# 4809-dip-th.net
KiCad netlist of a schematic drawn in EAGLE
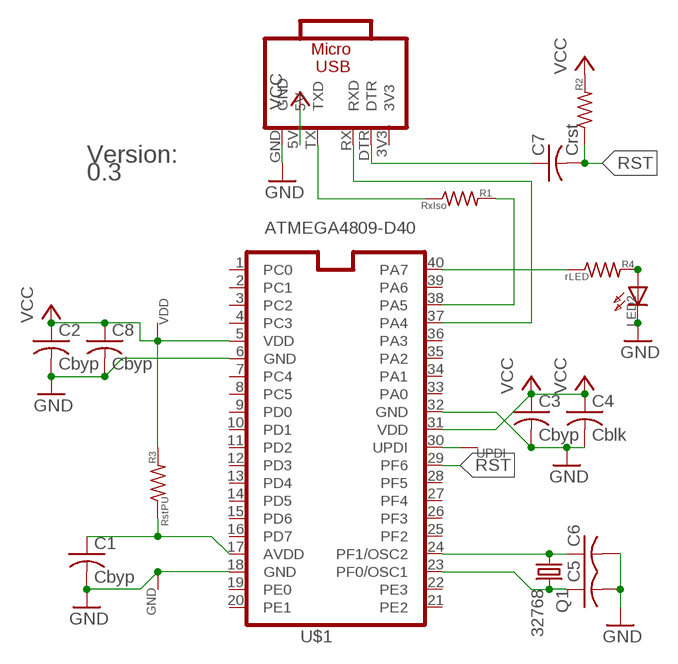
[diagram p0: schematic, sheet 1]

(export (version "E")
  (design (tool "Eeschema 10.0.6"))
  (components
    (comp (ref "C1")
      (value "Cbyp")
      (footprint "eagle-import:C025-025X050")
      (libsource (lib "eagle-import") (part "C-US-2.5MM"))
    )
    (comp (ref "C2")
      (value "Cbyp")
      (footprint "eagle-import:C025-025X050")
      (libsource (lib "eagle-import") (part "C-US-2.5MM"))
    )
    (comp (ref "C3")
      (value "Cbyp")
      (footprint "eagle-import:C025-025X050")
      (libsource (lib "eagle-import") (part "C-US-2.5MM"))
    )
    (comp (ref "C4")
      (value "Cblk")
      (footprint "eagle-import:C025-025X050")
      (libsource (lib "eagle-import") (part "C-US-2.5MM"))
    )
    (comp (ref "C5")
      (value "C-US-2.5MM")
      (footprint "eagle-import:C025-025X050")
      (libsource (lib "eagle-import") (part "C-US-2.5MM"))
    )
    (comp (ref "C6")
      (value "C-US-2.5MM")
      (footprint "eagle-import:C025-025X050")
      (libsource (lib "eagle-import") (part "C-US-2.5MM"))
    )
    (comp (ref "C7")
      (value "Crst")
      (footprint "eagle-import:C025-025X050")
      (libsource (lib "eagle-import") (part "C-US-2.5MM"))
    )
    (comp (ref "C8")
      (value "Cbyp")
      (footprint "eagle-import:C1206")
      (libsource (lib "eagle-import") (part "C-USC1206"))
    )
    (comp (ref "GND")
      (value "WIRE-R10")
      (footprint "eagle-import:VIA10")
      (libsource (lib "eagle-import") (part "WIRE-R10"))
    )
    (comp (ref "LED2")
      (value "LED3MM")
      (footprint "eagle-import:LED3-2S")
      (libsource (lib "eagle-import") (part "LED3MM"))
    )
    (comp (ref "MOD1")
      (value "CH340E-MODNOHOLES")
      (footprint "eagle-import:CH340E-MOD-NOHOLES")
      (libsource (lib "eagle-import") (part "CH340E-MODNOHOLES"))
    )
    (comp (ref "Q1")
      (value "32768")
      (footprint "eagle-import:TC26HL")
      (libsource (lib "eagle-import") (part "CRYSTALTC26HL"))
    )
    (comp (ref "R1")
      (value "RxIso")
      (footprint "eagle-import:0204_7")
      (libsource (lib "eagle-import") (part "R-US_0204/7"))
    )
    (comp (ref "R2")
      (value "R-US_0204/7")
      (footprint "eagle-import:0204_7")
      (libsource (lib "eagle-import") (part "R-US_0204/7"))
    )
    (comp (ref "R3")
      (value "RstPU")
      (footprint "eagle-import:R0805")
      (libsource (lib "eagle-import") (part "R-US_R0805"))
    )
    (comp (ref "R4")
      (value "rLED")
      (footprint "eagle-import:0204_7")
      (libsource (lib "eagle-import") (part "R-US_0204/7"))
    )
    (comp (ref "U$1")
      (value "ATMEGA4809-D40")
      (footprint "eagle-import:DIL40SOC")
      (libsource (lib "eagle-import") (part "ATMEGA4809-D40"))
    )
    (comp (ref "UPDI")
      (value "WIRE-R10")
      (footprint "eagle-import:VIA10")
      (libsource (lib "eagle-import") (part "WIRE-R10"))
    )
    (comp (ref "VDD")
      (value "WIRE-VIA8")
      (footprint "eagle-import:VIA8")
      (libsource (lib "eagle-import") (part "WIRE-VIA8"))
    )
    (comp (ref "VS1")
      (value "0.3")
      (footprint "eagle-import:VERSIONSTRING")
      (libsource (lib "eagle-import") (part "VERSIONSTRING"))
    )
  )
  (nets
    (net (code "1") (name "/3V3") (class "Default")
      (node (ref "MOD1") (pin "3V3") (pinfunction "3V3_3V3") (pintype "power_in"))
    )
    (net (code "2") (name "GND") (class "Default")
      (node (ref "C1") (pin "2") (pinfunction "2_2") (pintype "passive"))
      (node (ref "C2") (pin "2") (pinfunction "2_2") (pintype "passive"))
      (node (ref "C3") (pin "2") (pinfunction "2_2") (pintype "passive"))
      (node (ref "C4") (pin "2") (pinfunction "2_2") (pintype "passive"))
      (node (ref "C5") (pin "2") (pinfunction "2_2") (pintype "passive"))
      (node (ref "C6") (pin "2") (pinfunction "2_2") (pintype "passive"))
      (node (ref "C8") (pin "2") (pinfunction "2_2") (pintype "passive"))
      (node (ref "GND") (pin "P$1") (pinfunction "P$1_P$1") (pintype "bidirectional"))
      (node (ref "LED2") (pin "P$2") (pinfunction "C_P$2") (pintype "passive"))
      (node (ref "MOD1") (pin "GND") (pinfunction "GND_GND") (pintype "power_in"))
      (node (ref "U$1") (pin "18") (pinfunction "GND_18") (pintype "power_in"))
      (node (ref "U$1") (pin "32") (pinfunction "GND_32") (pintype "power_in"))
      (node (ref "U$1") (pin "6") (pinfunction "GND_6") (pintype "power_in"))
    )
    (net (code "3") (name "Net-(C7-Pad1)") (class "Default")
      (node (ref "C7") (pin "1") (pinfunction "1_1") (pintype "passive"))
      (node (ref "MOD1") (pin "DTR") (pinfunction "DTR_DTR") (pintype "output"))
    )
    (net (code "4") (name "Net-(LED2-A)") (class "Default")
      (node (ref "LED2") (pin "P$1") (pinfunction "A_P$1") (pintype "passive"))
      (node (ref "R4") (pin "2") (pinfunction "2_2") (pintype "passive"))
    )
    (net (code "5") (name "Net-(MOD1-RXD)") (class "Default")
      (node (ref "MOD1") (pin "RX") (pinfunction "RXD_RX") (pintype "input"))
      (node (ref "U$1") (pin "37") (pinfunction "PA4_37") (pintype "bidirectional"))
    )
    (net (code "6") (name "Net-(MOD1-TXD)") (class "Default")
      (node (ref "MOD1") (pin "TX") (pinfunction "TXD_TX") (pintype "output"))
      (node (ref "R1") (pin "1") (pinfunction "1_1") (pintype "passive"))
    )
    (net (code "7") (name "Net-(U$1-AVDD)") (class "Default")
      (node (ref "C1") (pin "1") (pinfunction "1_1") (pintype "passive"))
      (node (ref "R3") (pin "1") (pinfunction "1_1") (pintype "passive"))
      (node (ref "U$1") (pin "17") (pinfunction "AVDD_17") (pintype "power_in"))
    )
    (net (code "8") (name "Net-(U$1-PA5)") (class "Default")
      (node (ref "R1") (pin "2") (pinfunction "2_2") (pintype "passive"))
      (node (ref "U$1") (pin "38") (pinfunction "PA5_38") (pintype "bidirectional"))
    )
    (net (code "9") (name "Net-(U$1-PA7)") (class "Default")
      (node (ref "R4") (pin "1") (pinfunction "1_1") (pintype "passive"))
      (node (ref "U$1") (pin "40") (pinfunction "PA7_40") (pintype "bidirectional"))
    )
    (net (code "10") (name "Net-(U$1-PF0{slash}OSC1)") (class "Default")
      (node (ref "C5") (pin "1") (pinfunction "1_1") (pintype "passive"))
      (node (ref "Q1") (pin "2") (pinfunction "2_2") (pintype "passive"))
      (node (ref "U$1") (pin "23") (pinfunction "PF0/OSC1_23") (pintype "bidirectional"))
    )
    (net (code "11") (name "Net-(U$1-PF1{slash}OSC2)") (class "Default")
      (node (ref "C6") (pin "1") (pinfunction "1_1") (pintype "passive"))
      (node (ref "Q1") (pin "1") (pinfunction "1_1") (pintype "passive"))
      (node (ref "U$1") (pin "24") (pinfunction "PF1/OSC2_24") (pintype "bidirectional"))
    )
    (net (code "12") (name "Net-(U$1-UPDI)") (class "Default")
      (node (ref "U$1") (pin "30") (pinfunction "UPDI_30") (pintype "bidirectional"))
      (node (ref "UPDI") (pin "P$1") (pinfunction "P$1_P$1") (pintype "bidirectional"))
    )
    (net (code "13") (name "RST") (class "Default")
      (node (ref "C7") (pin "2") (pinfunction "2_2") (pintype "passive"))
      (node (ref "R2") (pin "1") (pinfunction "1_1") (pintype "passive"))
      (node (ref "U$1") (pin "29") (pinfunction "PF6_29") (pintype "bidirectional"))
    )
    (net (code "14") (name "VCC") (class "Default")
      (node (ref "C2") (pin "1") (pinfunction "1_1") (pintype "passive"))
      (node (ref "C3") (pin "1") (pinfunction "1_1") (pintype "passive"))
      (node (ref "C4") (pin "1") (pinfunction "1_1") (pintype "passive"))
      (node (ref "C8") (pin "1") (pinfunction "1_1") (pintype "passive"))
      (node (ref "MOD1") (pin "5V") (pinfunction "5V_5V") (pintype "power_in"))
      (node (ref "R2") (pin "2") (pinfunction "2_2") (pintype "passive"))
      (node (ref "R3") (pin "2") (pinfunction "2_2") (pintype "passive"))
      (node (ref "U$1") (pin "31") (pinfunction "VDD_31") (pintype "power_in"))
      (node (ref "U$1") (pin "5") (pinfunction "VDD_5") (pintype "power_in"))
      (node (ref "VDD") (pin "P$1") (pinfunction "P$1_P$1") (pintype "bidirectional"))
    )
    (net (code "15") (name "unconnected-(U$1-PA0-Pad33)") (class "Default")
      (node (ref "U$1") (pin "33") (pinfunction "PA0_33") (pintype "bidirectional"))
    )
    (net (code "16") (name "unconnected-(U$1-PA1-Pad34)") (class "Default")
      (node (ref "U$1") (pin "34") (pinfunction "PA1_34") (pintype "bidirectional"))
    )
    (net (code "17") (name "unconnected-(U$1-PA2-Pad35)") (class "Default")
      (node (ref "U$1") (pin "35") (pinfunction "PA2_35") (pintype "bidirectional"))
    )
    (net (code "18") (name "unconnected-(U$1-PA3-Pad36)") (class "Default")
      (node (ref "U$1") (pin "36") (pinfunction "PA3_36") (pintype "bidirectional"))
    )
    (net (code "19") (name "unconnected-(U$1-PA6-Pad39)") (class "Default")
      (node (ref "U$1") (pin "39") (pinfunction "PA6_39") (pintype "bidirectional"))
    )
    (net (code "20") (name "unconnected-(U$1-PC0-Pad1)") (class "Default")
      (node (ref "U$1") (pin "1") (pinfunction "PC0_1") (pintype "bidirectional"))
    )
    (net (code "21") (name "unconnected-(U$1-PC1-Pad2)") (class "Default")
      (node (ref "U$1") (pin "2") (pinfunction "PC1_2") (pintype "bidirectional"))
    )
    (net (code "22") (name "unconnected-(U$1-PC2-Pad3)") (class "Default")
      (node (ref "U$1") (pin "3") (pinfunction "PC2_3") (pintype "bidirectional"))
    )
    (net (code "23") (name "unconnected-(U$1-PC3-Pad4)") (class "Default")
      (node (ref "U$1") (pin "4") (pinfunction "PC3_4") (pintype "bidirectional"))
    )
    (net (code "24") (name "unconnected-(U$1-PC4-Pad7)") (class "Default")
      (node (ref "U$1") (pin "7") (pinfunction "PC4_7") (pintype "bidirectional"))
    )
    (net (code "25") (name "unconnected-(U$1-PC5-Pad8)") (class "Default")
      (node (ref "U$1") (pin "8") (pinfunction "PC5_8") (pintype "bidirectional"))
    )
    (net (code "26") (name "unconnected-(U$1-PD0-Pad9)") (class "Default")
      (node (ref "U$1") (pin "9") (pinfunction "PD0_9") (pintype "bidirectional"))
    )
    (net (code "27") (name "unconnected-(U$1-PD1-Pad10)") (class "Default")
      (node (ref "U$1") (pin "10") (pinfunction "PD1_10") (pintype "bidirectional"))
    )
    (net (code "28") (name "unconnected-(U$1-PD2-Pad11)") (class "Default")
      (node (ref "U$1") (pin "11") (pinfunction "PD2_11") (pintype "bidirectional"))
    )
    (net (code "29") (name "unconnected-(U$1-PD3-Pad12)") (class "Default")
      (node (ref "U$1") (pin "12") (pinfunction "PD3_12") (pintype "bidirectional"))
    )
    (net (code "30") (name "unconnected-(U$1-PD4-Pad13)") (class "Default")
      (node (ref "U$1") (pin "13") (pinfunction "PD4_13") (pintype "bidirectional"))
    )
    (net (code "31") (name "unconnected-(U$1-PD5-Pad14)") (class "Default")
      (node (ref "U$1") (pin "14") (pinfunction "PD5_14") (pintype "bidirectional"))
    )
    (net (code "32") (name "unconnected-(U$1-PD6-Pad15)") (class "Default")
      (node (ref "U$1") (pin "15") (pinfunction "PD6_15") (pintype "bidirectional"))
    )
    (net (code "33") (name "unconnected-(U$1-PD7-Pad16)") (class "Default")
      (node (ref "U$1") (pin "16") (pinfunction "PD7_16") (pintype "bidirectional"))
    )
    (net (code "34") (name "unconnected-(U$1-PE0-Pad19)") (class "Default")
      (node (ref "U$1") (pin "19") (pinfunction "PE0_19") (pintype "bidirectional"))
    )
    (net (code "35") (name "unconnected-(U$1-PE1-Pad20)") (class "Default")
      (node (ref "U$1") (pin "20") (pinfunction "PE1_20") (pintype "bidirectional"))
    )
    (net (code "36") (name "unconnected-(U$1-PE2-Pad21)") (class "Default")
      (node (ref "U$1") (pin "21") (pinfunction "PE2_21") (pintype "bidirectional"))
    )
    (net (code "37") (name "unconnected-(U$1-PE3-Pad22)") (class "Default")
      (node (ref "U$1") (pin "22") (pinfunction "PE3_22") (pintype "bidirectional"))
    )
    (net (code "38") (name "unconnected-(U$1-PF2-Pad25)") (class "Default")
      (node (ref "U$1") (pin "25") (pinfunction "PF2_25") (pintype "bidirectional"))
    )
    (net (code "39") (name "unconnected-(U$1-PF3-Pad26)") (class "Default")
      (node (ref "U$1") (pin "26") (pinfunction "PF3_26") (pintype "bidirectional"))
    )
    (net (code "40") (name "unconnected-(U$1-PF4-Pad27)") (class "Default")
      (node (ref "U$1") (pin "27") (pinfunction "PF4_27") (pintype "bidirectional"))
    )
    (net (code "41") (name "unconnected-(U$1-PF5-Pad28)") (class "Default")
      (node (ref "U$1") (pin "28") (pinfunction "PF5_28") (pintype "bidirectional"))
    )
  )
)
